# Buttons.net
KiCad netlist of a schematic drawn in Altium Designer
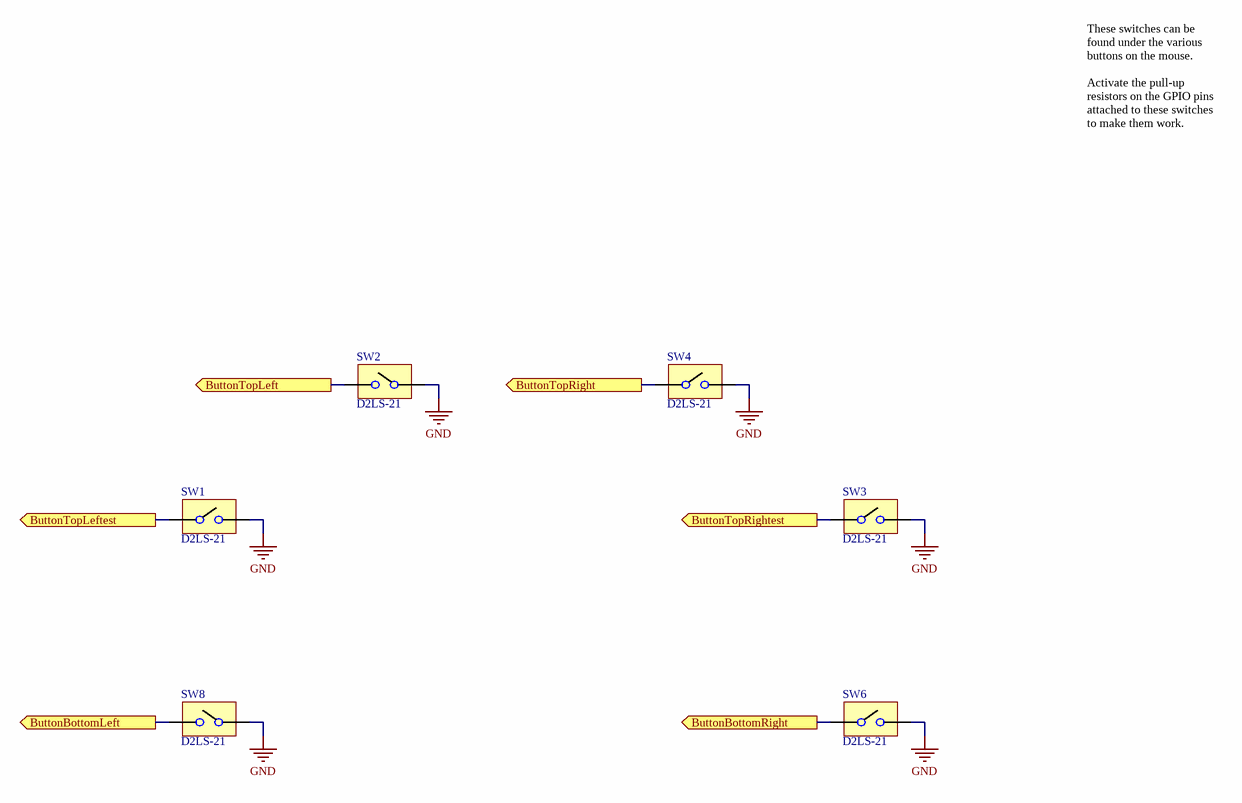
[diagram p0: Buttons.SchDoc]

(export (version "E")
  (design (tool "Eeschema 10.0.6"))
  (components
    (comp (ref "SW1")
      (value "D2LS-21")
      (footprint "D2LS-21")
      (description "Compact Surface-mounting Switch for long durability")
      (libsource (lib "Switches") (part "D2LS-21"))
    )
    (comp (ref "SW2")
      (value "D2LS-21")
      (footprint "D2LS-21")
      (description "Compact Surface-mounting Switch for long durability")
      (libsource (lib "") (part "D2LS-21_1"))
    )
    (comp (ref "SW3")
      (value "D2LS-21")
      (footprint "D2LS-21")
      (description "Compact Surface-mounting Switch for long durability")
      (libsource (lib "Switches") (part "D2LS-21"))
    )
    (comp (ref "SW4")
      (value "D2LS-21")
      (footprint "D2LS-21")
      (description "Compact Surface-mounting Switch for long durability")
      (libsource (lib "Switches") (part "D2LS-21"))
    )
    (comp (ref "SW6")
      (value "D2LS-21")
      (footprint "D2LS-21")
      (description "Compact Surface-mounting Switch for long durability")
      (libsource (lib "Switches") (part "D2LS-21"))
    )
    (comp (ref "SW8")
      (value "D2LS-21")
      (footprint "D2LS-21")
      (description "Compact Surface-mounting Switch for long durability")
      (libsource (lib "") (part "D2LS-21_1"))
    )
  )
  (nets
    (net (code "1") (name "/ButtonBottomLeft") (class "Default")
      (node (ref "SW8") (pin "B") (pinfunction "B_B") (pintype "passive"))
    )
    (net (code "2") (name "/ButtonBottomRight") (class "Default")
      (node (ref "SW6") (pin "A") (pinfunction "A_A") (pintype "passive"))
    )
    (net (code "3") (name "/ButtonTopLeft") (class "Default")
      (node (ref "SW2") (pin "B") (pinfunction "B_B") (pintype "passive"))
    )
    (net (code "4") (name "/ButtonTopLeftest") (class "Default")
      (node (ref "SW1") (pin "A") (pinfunction "A_A") (pintype "passive"))
    )
    (net (code "5") (name "/ButtonTopRight") (class "Default")
      (node (ref "SW4") (pin "A") (pinfunction "A_A") (pintype "passive"))
    )
    (net (code "6") (name "/ButtonTopRightest") (class "Default")
      (node (ref "SW3") (pin "A") (pinfunction "A_A") (pintype "passive"))
    )
    (net (code "7") (name "GND") (class "Default")
      (node (ref "SW1") (pin "B") (pinfunction "B_B") (pintype "passive"))
      (node (ref "SW2") (pin "A") (pinfunction "A_A") (pintype "passive"))
      (node (ref "SW3") (pin "B") (pinfunction "B_B") (pintype "passive"))
      (node (ref "SW4") (pin "B") (pinfunction "B_B") (pintype "passive"))
      (node (ref "SW6") (pin "B") (pinfunction "B_B") (pintype "passive"))
      (node (ref "SW8") (pin "A") (pinfunction "A_A") (pintype "passive"))
    )
  )
)
